# RJ-45_v1_1_Top_Routed.net
KiCad netlist of a schematic drawn in EAGLE
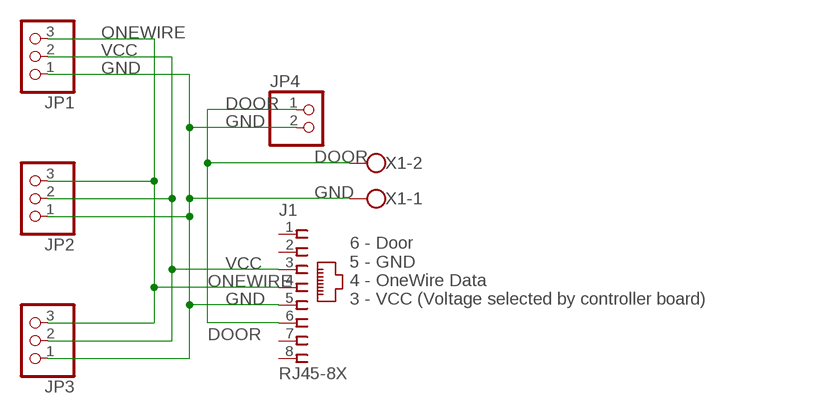
[diagram p0: schematic, sheet 1]

(export (version "E")
  (design (tool "Eeschema 10.0.6"))
  (components
    (comp (ref "J1")
      (value "RJ45-8X")
      (footprint "eagle-import:RJ45-NO-SHIELD")
      (libsource (lib "eagle-import") (part "RJ45-8X"))
    )
    (comp (ref "JP1")
      (value "PINHD-1X3")
      (footprint "eagle-import:1X03")
      (libsource (lib "eagle-import") (part "PINHD-1X3"))
    )
    (comp (ref "JP2")
      (value "PINHD-1X3")
      (footprint "eagle-import:1X03")
      (libsource (lib "eagle-import") (part "PINHD-1X3"))
    )
    (comp (ref "JP3")
      (value "PINHD-1X3")
      (footprint "eagle-import:1X03")
      (libsource (lib "eagle-import") (part "PINHD-1X3"))
    )
    (comp (ref "JP4")
      (value "PINHD-1X2")
      (footprint "eagle-import:1X02")
      (libsource (lib "eagle-import") (part "PINHD-1X2"))
    )
    (comp (ref "X1")
      (value "W237-102")
      (footprint "eagle-import:W237-102")
      (fields (field (name "MPN") "237-102"))
      (libsource (lib "eagle-import") (part "W237-102"))
    )
  )
  (nets
    (net (code "1") (name "/DOOR") (class "Default")
      (node (ref "J1") (pin "6") (pinfunction "6_6") (pintype "passive"))
      (node (ref "JP4") (pin "1") (pinfunction "1_1") (pintype "passive"))
      (node (ref "X1") (pin "2") (pinfunction "KL_2") (pintype "passive"))
    )
    (net (code "2") (name "/GND") (class "Default")
      (node (ref "J1") (pin "5") (pinfunction "5_5") (pintype "passive"))
      (node (ref "JP1") (pin "1") (pinfunction "1_1") (pintype "passive"))
      (node (ref "JP2") (pin "1") (pinfunction "1_1") (pintype "passive"))
      (node (ref "JP3") (pin "1") (pinfunction "1_1") (pintype "passive"))
      (node (ref "JP4") (pin "2") (pinfunction "2_2") (pintype "passive"))
      (node (ref "X1") (pin "1") (pinfunction "KL_1") (pintype "passive"))
    )
    (net (code "3") (name "/ONEWIRE") (class "Default")
      (node (ref "J1") (pin "4") (pinfunction "4_4") (pintype "passive"))
      (node (ref "JP1") (pin "3") (pinfunction "3_3") (pintype "passive"))
      (node (ref "JP2") (pin "3") (pinfunction "3_3") (pintype "passive"))
      (node (ref "JP3") (pin "3") (pinfunction "3_3") (pintype "passive"))
    )
    (net (code "4") (name "/VCC") (class "Default")
      (node (ref "J1") (pin "3") (pinfunction "3_3") (pintype "passive"))
      (node (ref "JP1") (pin "2") (pinfunction "2_2") (pintype "passive"))
      (node (ref "JP2") (pin "2") (pinfunction "2_2") (pintype "passive"))
      (node (ref "JP3") (pin "2") (pinfunction "2_2") (pintype "passive"))
    )
    (net (code "5") (name "unconnected-(J1-Pad1)") (class "Default")
      (node (ref "J1") (pin "1") (pinfunction "1_1") (pintype "passive"))
    )
    (net (code "6") (name "unconnected-(J1-Pad2)") (class "Default")
      (node (ref "J1") (pin "2") (pinfunction "2_2") (pintype "passive"))
    )
    (net (code "7") (name "unconnected-(J1-Pad7)") (class "Default")
      (node (ref "J1") (pin "7") (pinfunction "7_7") (pintype "passive"))
    )
    (net (code "8") (name "unconnected-(J1-Pad8)") (class "Default")
      (node (ref "J1") (pin "8") (pinfunction "8_8") (pintype "passive"))
    )
  )
)
